# OPNpool_r1_0.net
KiCad netlist of a schematic drawn in EAGLE
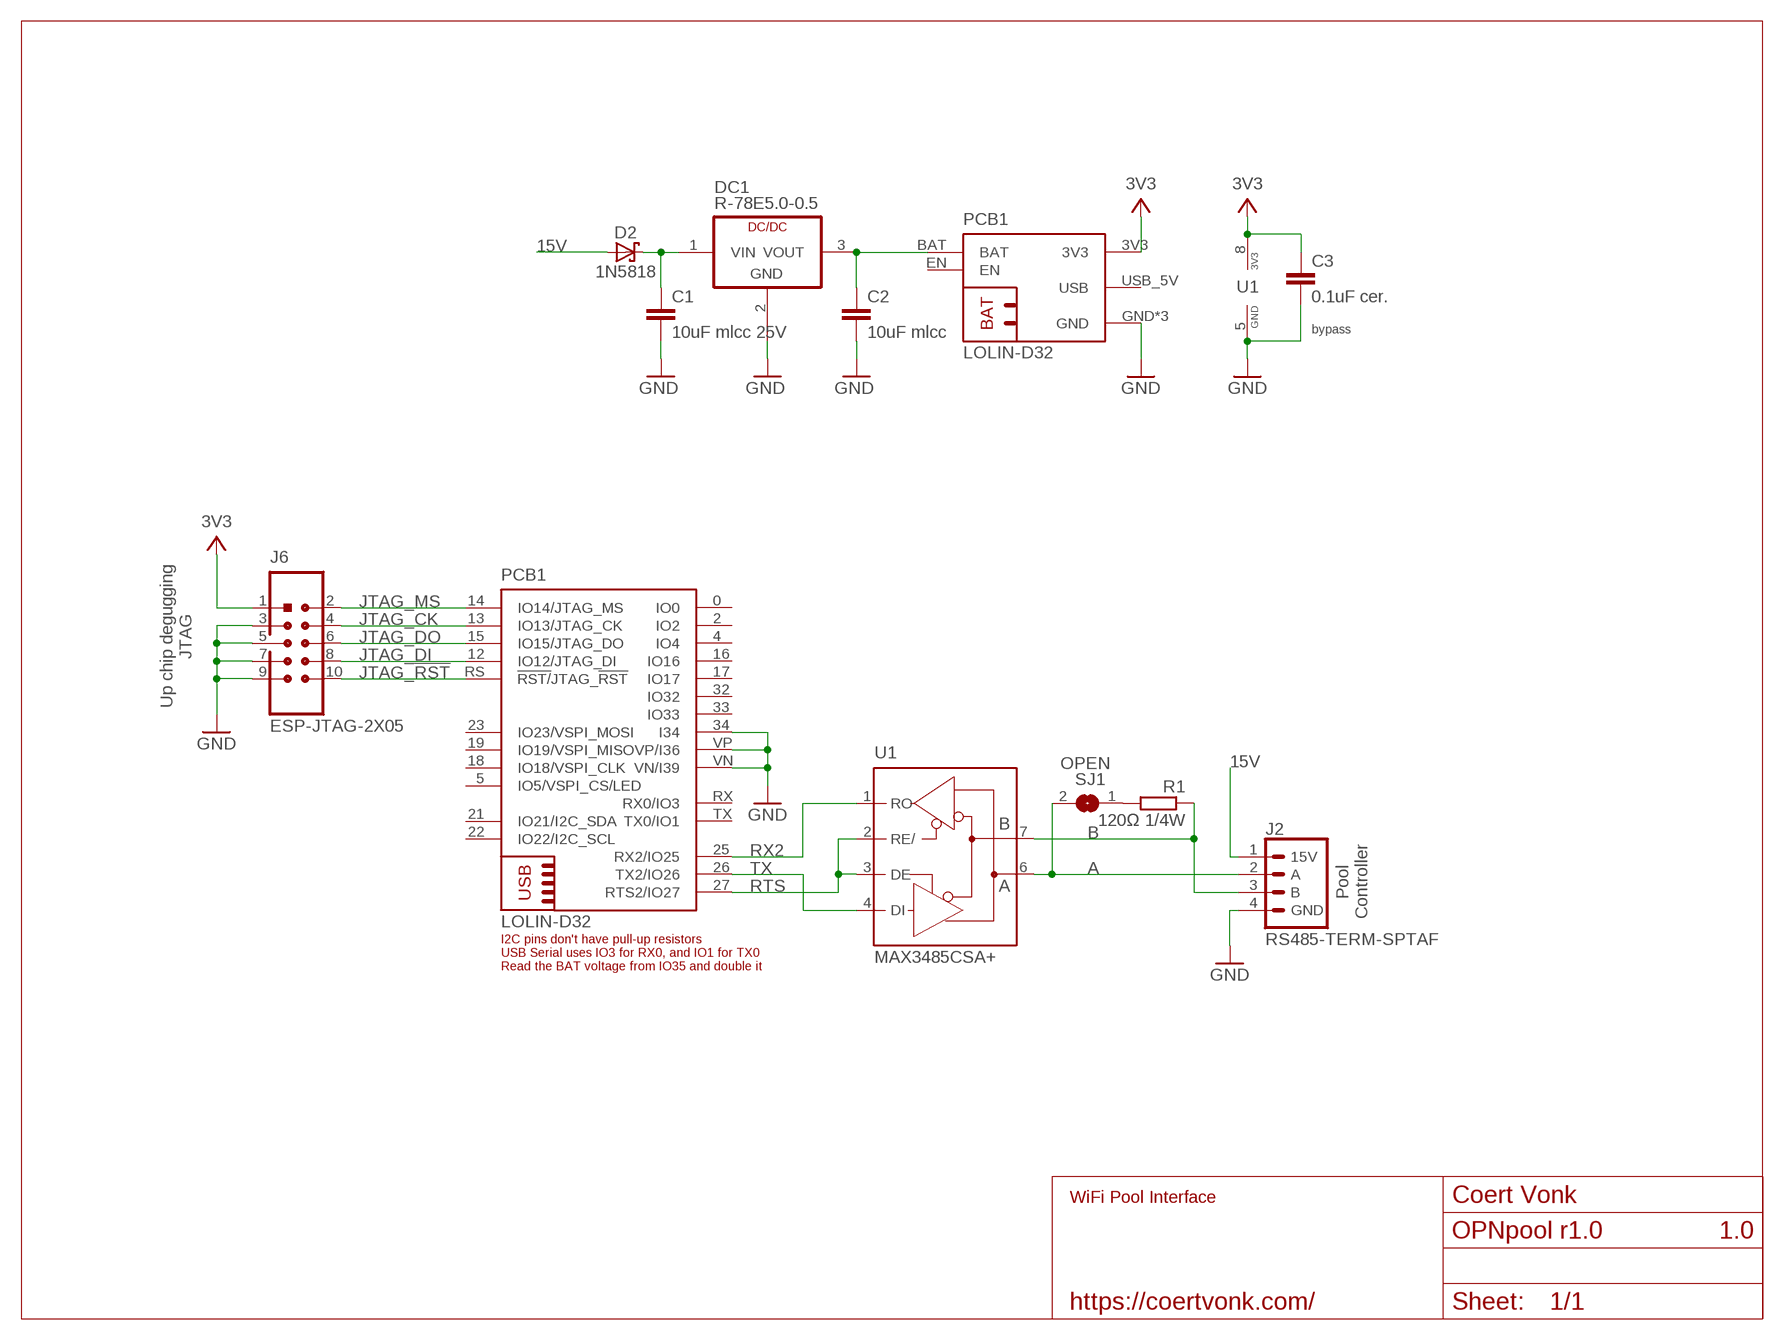
[diagram p0: schematic, sheet 1]

(export (version "E")
  (design (tool "Eeschema 10.0.6"))
  (components
    (comp (ref "C1")
      (value "10uF mlcc 25V")
      (footprint "eagle-import:C0805K")
      (fields (field (name "MANF") "Murata Electronics"))
      (libsource (lib "eagle-import") (part "C-EUC0805K"))
    )
    (comp (ref "C2")
      (value "10uF mlcc")
      (footprint "eagle-import:C0805K")
      (fields (field (name "MANF") "Murata Electronics"))
      (libsource (lib "eagle-import") (part "C-EUC0805K"))
    )
    (comp (ref "C3")
      (value "0.1uF cer.")
      (footprint "eagle-import:C0805K")
      (fields (field (name "MANF") "KEMET"))
      (libsource (lib "eagle-import") (part "C-EUC0805K"))
    )
    (comp (ref "D2")
      (value "1N5818")
      (footprint "eagle-import:DO41-7.6")
      (fields (field (name "MANF") "Rectron"))
      (libsource (lib "eagle-import") (part "1N5818"))
    )
    (comp (ref "DC1")
      (value "R-78E5.0-0.5")
      (footprint "eagle-import:SIP3")
      (fields (field (name "MANF") "RECOM Power"))
      (libsource (lib "eagle-import") (part "R-78E-0.55.0"))
    )
    (comp (ref "J2")
      (value "RS485-TERM-SPTAF")
      (footprint "eagle-import:SPTAF1_4-5,0-LL")
      (fields (field (name "MANF") "Phoenix Contact"))
      (libsource (lib "eagle-import") (part "RS485-TERM-SPTAF"))
    )
    (comp (ref "J6")
      (value "ESP-JTAG-2X05")
      (footprint "eagle-import:2X05_SHROUDED")
      (fields (field (name "MANF") "Molex"))
      (libsource (lib "eagle-import") (part "ESP-JTAG-2X05"))
    )
    (comp (ref "PCB1")
      (value "LOLIN-D32")
      (footprint "eagle-import:LOLIN-D32")
      (fields
        (field (name "MANF") "WEMOS Electronics")
        (field (name "ALIEXPRESS#") "32808551116")
        (field (name "MANF#") "D32")
      )
      (libsource (lib "eagle-import") (part "LOLIN-D32"))
    )
    (comp (ref "R1")
      (value "120Ω 1/4W")
      (footprint "eagle-import:R0805")
      (fields (field (name "MANF") "Bourns"))
      (libsource (lib "eagle-import") (part "R-EU_R0805"))
    )
    (comp (ref "SJ1")
      (value "OPEN")
      (footprint "eagle-import:SJ")
      (libsource (lib "eagle-import") (part "SJ"))
    )
    (comp (ref "U1")
      (value "MAX3485CSA+")
      (footprint "eagle-import:SO08")
      (fields
        (field (name "MF") "MAXIM")
        (field (name "MPN") "MAX481CSA")
        (field (name "MANF") "Maxim Integrated")
        (field (name "MANF#") "MAX3485CSA+")
        (field (name "MOUSER#") "700-MAX3485CSA")
      )
      (libsource (lib "eagle-import") (part "MAX3485CSA+"))
    )
  )
  (nets
    (net (code "1") (name "/15V") (class "Default")
      (node (ref "D2") (pin "A") (pinfunction "A_A") (pintype "passive"))
      (node (ref "J2") (pin "1") (pinfunction "15V_1") (pintype "power_in"))
    )
    (net (code "2") (name "/A") (class "Default")
      (node (ref "J2") (pin "2") (pinfunction "A_2") (pintype "passive"))
      (node (ref "SJ1") (pin "2") (pinfunction "2_2") (pintype "passive"))
      (node (ref "U1") (pin "6") (pinfunction "A_6") (pintype "passive"))
    )
    (net (code "3") (name "/B") (class "Default")
      (node (ref "J2") (pin "3") (pinfunction "B_3") (pintype "passive"))
      (node (ref "R1") (pin "1") (pinfunction "1_1") (pintype "passive"))
      (node (ref "U1") (pin "7") (pinfunction "B_7") (pintype "passive"))
    )
    (net (code "4") (name "/JTAG_CK") (class "Default")
      (node (ref "J6") (pin "4") (pinfunction "TCK_4") (pintype "passive"))
      (node (ref "PCB1") (pin "13") (pinfunction "IO13/JTAG_CK_13") (pintype "bidirectional"))
    )
    (net (code "5") (name "/JTAG_DI") (class "Default")
      (node (ref "J6") (pin "8") (pinfunction "TDI_8") (pintype "passive"))
      (node (ref "PCB1") (pin "12") (pinfunction "IO12/JTAG_DI_12") (pintype "bidirectional"))
    )
    (net (code "6") (name "/JTAG_DO") (class "Default")
      (node (ref "J6") (pin "6") (pinfunction "TDO_6") (pintype "passive"))
      (node (ref "PCB1") (pin "15") (pinfunction "IO15/JTAG_DO_15") (pintype "bidirectional"))
    )
    (net (code "7") (name "/JTAG_MS") (class "Default")
      (node (ref "J6") (pin "2") (pinfunction "TMS_2") (pintype "passive"))
      (node (ref "PCB1") (pin "14") (pinfunction "IO14/JTAG_MS_14") (pintype "bidirectional"))
    )
    (net (code "8") (name "/JTAG_~{RST}") (class "Default")
      (node (ref "J6") (pin "10") (pinfunction "NC_10") (pintype "passive"))
      (node (ref "PCB1") (pin "RS") (pinfunction "~{RST/}JTAG_~{RST}_RS") (pintype "input"))
    )
    (net (code "9") (name "/RTS") (class "Default")
      (node (ref "PCB1") (pin "27") (pinfunction "RTS2/IO27_27") (pintype "bidirectional"))
      (node (ref "U1") (pin "2") (pinfunction "RE/_2") (pintype "input"))
      (node (ref "U1") (pin "3") (pinfunction "DE_3") (pintype "input"))
    )
    (net (code "10") (name "/RX2") (class "Default")
      (node (ref "PCB1") (pin "25") (pinfunction "RX2/IO25_25") (pintype "bidirectional"))
      (node (ref "U1") (pin "1") (pinfunction "RO_1") (pintype "output"))
    )
    (net (code "11") (name "/TX") (class "Default")
      (node (ref "PCB1") (pin "26") (pinfunction "TX2/IO26_26") (pintype "bidirectional"))
      (node (ref "U1") (pin "4") (pinfunction "DI_4") (pintype "input"))
    )
    (net (code "12") (name "/USB") (class "Default")
      (node (ref "PCB1") (pin "USB_5V") (pinfunction "USB_USB_5V") (pintype "power_in"))
    )
    (net (code "13") (name "3V3") (class "Default")
      (node (ref "C3") (pin "1") (pinfunction "1_1") (pintype "passive"))
      (node (ref "J6") (pin "1") (pinfunction "3V3_1") (pintype "power_in"))
      (node (ref "PCB1") (pin "3V3") (pinfunction "3V3_3V3") (pintype "power_in"))
      (node (ref "U1") (pin "8") (pinfunction "VCC_8") (pintype "passive"))
    )
    (net (code "14") (name "GND") (class "Default")
      (node (ref "C1") (pin "2") (pinfunction "2_2") (pintype "passive"))
      (node (ref "C2") (pin "2") (pinfunction "2_2") (pintype "passive"))
      (node (ref "C3") (pin "2") (pinfunction "2_2") (pintype "passive"))
      (node (ref "DC1") (pin "2") (pinfunction "GND_2") (pintype "power_in"))
      (node (ref "J2") (pin "4") (pinfunction "GND_4") (pintype "power_in"))
      (node (ref "J6") (pin "3") (pinfunction "GND_3") (pintype "power_in"))
      (node (ref "J6") (pin "5") (pinfunction "GND_5") (pintype "power_in"))
      (node (ref "J6") (pin "7") (pinfunction "GND_7") (pintype "power_in"))
      (node (ref "J6") (pin "9") (pinfunction "GND_9") (pintype "power_in"))
      (node (ref "PCB1") (pin "34") (pinfunction "I34_34") (pintype "input"))
      (node (ref "PCB1") (pin "GND") (pinfunction "GND_GND") (pintype "power_in"))
      (node (ref "PCB1") (pin "GND@1") (pinfunction "GND_GND@1") (pintype "power_in"))
      (node (ref "PCB1") (pin "GND@2") (pinfunction "GND_GND@2") (pintype "power_in"))
      (node (ref "PCB1") (pin "VN") (pinfunction "VN/I39_VN") (pintype "input"))
      (node (ref "PCB1") (pin "VP") (pinfunction "VP/I36_VP") (pintype "input"))
      (node (ref "U1") (pin "5") (pinfunction "GND_5") (pintype "power_in"))
    )
    (net (code "15") (name "Net-(DC1-VIN)") (class "Default")
      (node (ref "C1") (pin "1") (pinfunction "1_1") (pintype "passive"))
      (node (ref "D2") (pin "C") (pinfunction "C_C") (pintype "passive"))
      (node (ref "DC1") (pin "1") (pinfunction "VIN_1") (pintype "power_in"))
    )
    (net (code "16") (name "Net-(DC1-VOUT)") (class "Default")
      (node (ref "C2") (pin "1") (pinfunction "1_1") (pintype "passive"))
      (node (ref "DC1") (pin "3") (pinfunction "VOUT_3") (pintype "power_in"))
      (node (ref "PCB1") (pin "BAT") (pinfunction "BAT_BAT") (pintype "power_in"))
    )
    (net (code "17") (name "Net-(R1-Pad2)") (class "Default")
      (node (ref "R1") (pin "2") (pinfunction "2_2") (pintype "passive"))
      (node (ref "SJ1") (pin "1") (pinfunction "1_1") (pintype "passive"))
    )
    (net (code "18") (name "unconnected-(PCB1-PadEN)") (class "Default")
      (node (ref "PCB1") (pin "EN") (pinfunction "EN_EN") (pintype "passive"))
    )
    (net (code "19") (name "unconnected-(PCB1A-IO0-Pad0)") (class "Default")
      (node (ref "PCB1") (pin "0") (pinfunction "IO0_0") (pintype "bidirectional"))
    )
    (net (code "20") (name "unconnected-(PCB1A-IO2-Pad2)") (class "Default")
      (node (ref "PCB1") (pin "2") (pinfunction "IO2_2") (pintype "bidirectional"))
    )
    (net (code "21") (name "unconnected-(PCB1A-IO4-Pad4)") (class "Default")
      (node (ref "PCB1") (pin "4") (pinfunction "IO4_4") (pintype "bidirectional"))
    )
    (net (code "22") (name "unconnected-(PCB1A-IO5{slash}VSPI_CS{slash}LED-Pad5)") (class "Default")
      (node (ref "PCB1") (pin "5") (pinfunction "IO5/VSPI_CS/LED_5") (pintype "bidirectional"))
    )
    (net (code "23") (name "unconnected-(PCB1A-IO16-Pad16)") (class "Default")
      (node (ref "PCB1") (pin "16") (pinfunction "IO16_16") (pintype "bidirectional"))
    )
    (net (code "24") (name "unconnected-(PCB1A-IO17-Pad17)") (class "Default")
      (node (ref "PCB1") (pin "17") (pinfunction "IO17_17") (pintype "bidirectional"))
    )
    (net (code "25") (name "unconnected-(PCB1A-IO18{slash}VSPI_CLK-Pad18)") (class "Default")
      (node (ref "PCB1") (pin "18") (pinfunction "IO18/VSPI_CLK_18") (pintype "bidirectional"))
    )
    (net (code "26") (name "unconnected-(PCB1A-IO19{slash}VSPI_MISO-Pad19)") (class "Default")
      (node (ref "PCB1") (pin "19") (pinfunction "IO19/VSPI_MISO_19") (pintype "bidirectional"))
    )
    (net (code "27") (name "unconnected-(PCB1A-IO21{slash}I2C_SDA-Pad21)") (class "Default")
      (node (ref "PCB1") (pin "21") (pinfunction "IO21/I2C_SDA_21") (pintype "bidirectional"))
    )
    (net (code "28") (name "unconnected-(PCB1A-IO22{slash}I2C_SCL-Pad22)") (class "Default")
      (node (ref "PCB1") (pin "22") (pinfunction "IO22/I2C_SCL_22") (pintype "bidirectional"))
    )
    (net (code "29") (name "unconnected-(PCB1A-IO23{slash}VSPI_MOSI-Pad23)") (class "Default")
      (node (ref "PCB1") (pin "23") (pinfunction "IO23/VSPI_MOSI_23") (pintype "bidirectional"))
    )
    (net (code "30") (name "unconnected-(PCB1A-IO32-Pad32)") (class "Default")
      (node (ref "PCB1") (pin "32") (pinfunction "IO32_32") (pintype "bidirectional"))
    )
    (net (code "31") (name "unconnected-(PCB1A-IO33-Pad33)") (class "Default")
      (node (ref "PCB1") (pin "33") (pinfunction "IO33_33") (pintype "bidirectional"))
    )
    (net (code "32") (name "unconnected-(PCB1A-RX0{slash}IO3-PadRX)") (class "Default")
      (node (ref "PCB1") (pin "RX") (pinfunction "RX0/IO3_RX") (pintype "bidirectional"))
    )
    (net (code "33") (name "unconnected-(PCB1A-TX0{slash}IO1-PadTX)") (class "Default")
      (node (ref "PCB1") (pin "TX") (pinfunction "TX0/IO1_TX") (pintype "bidirectional"))
    )
  )
)
